# test_rj45-12_THT.net
KiCad netlist of a schematic drawn in EAGLE
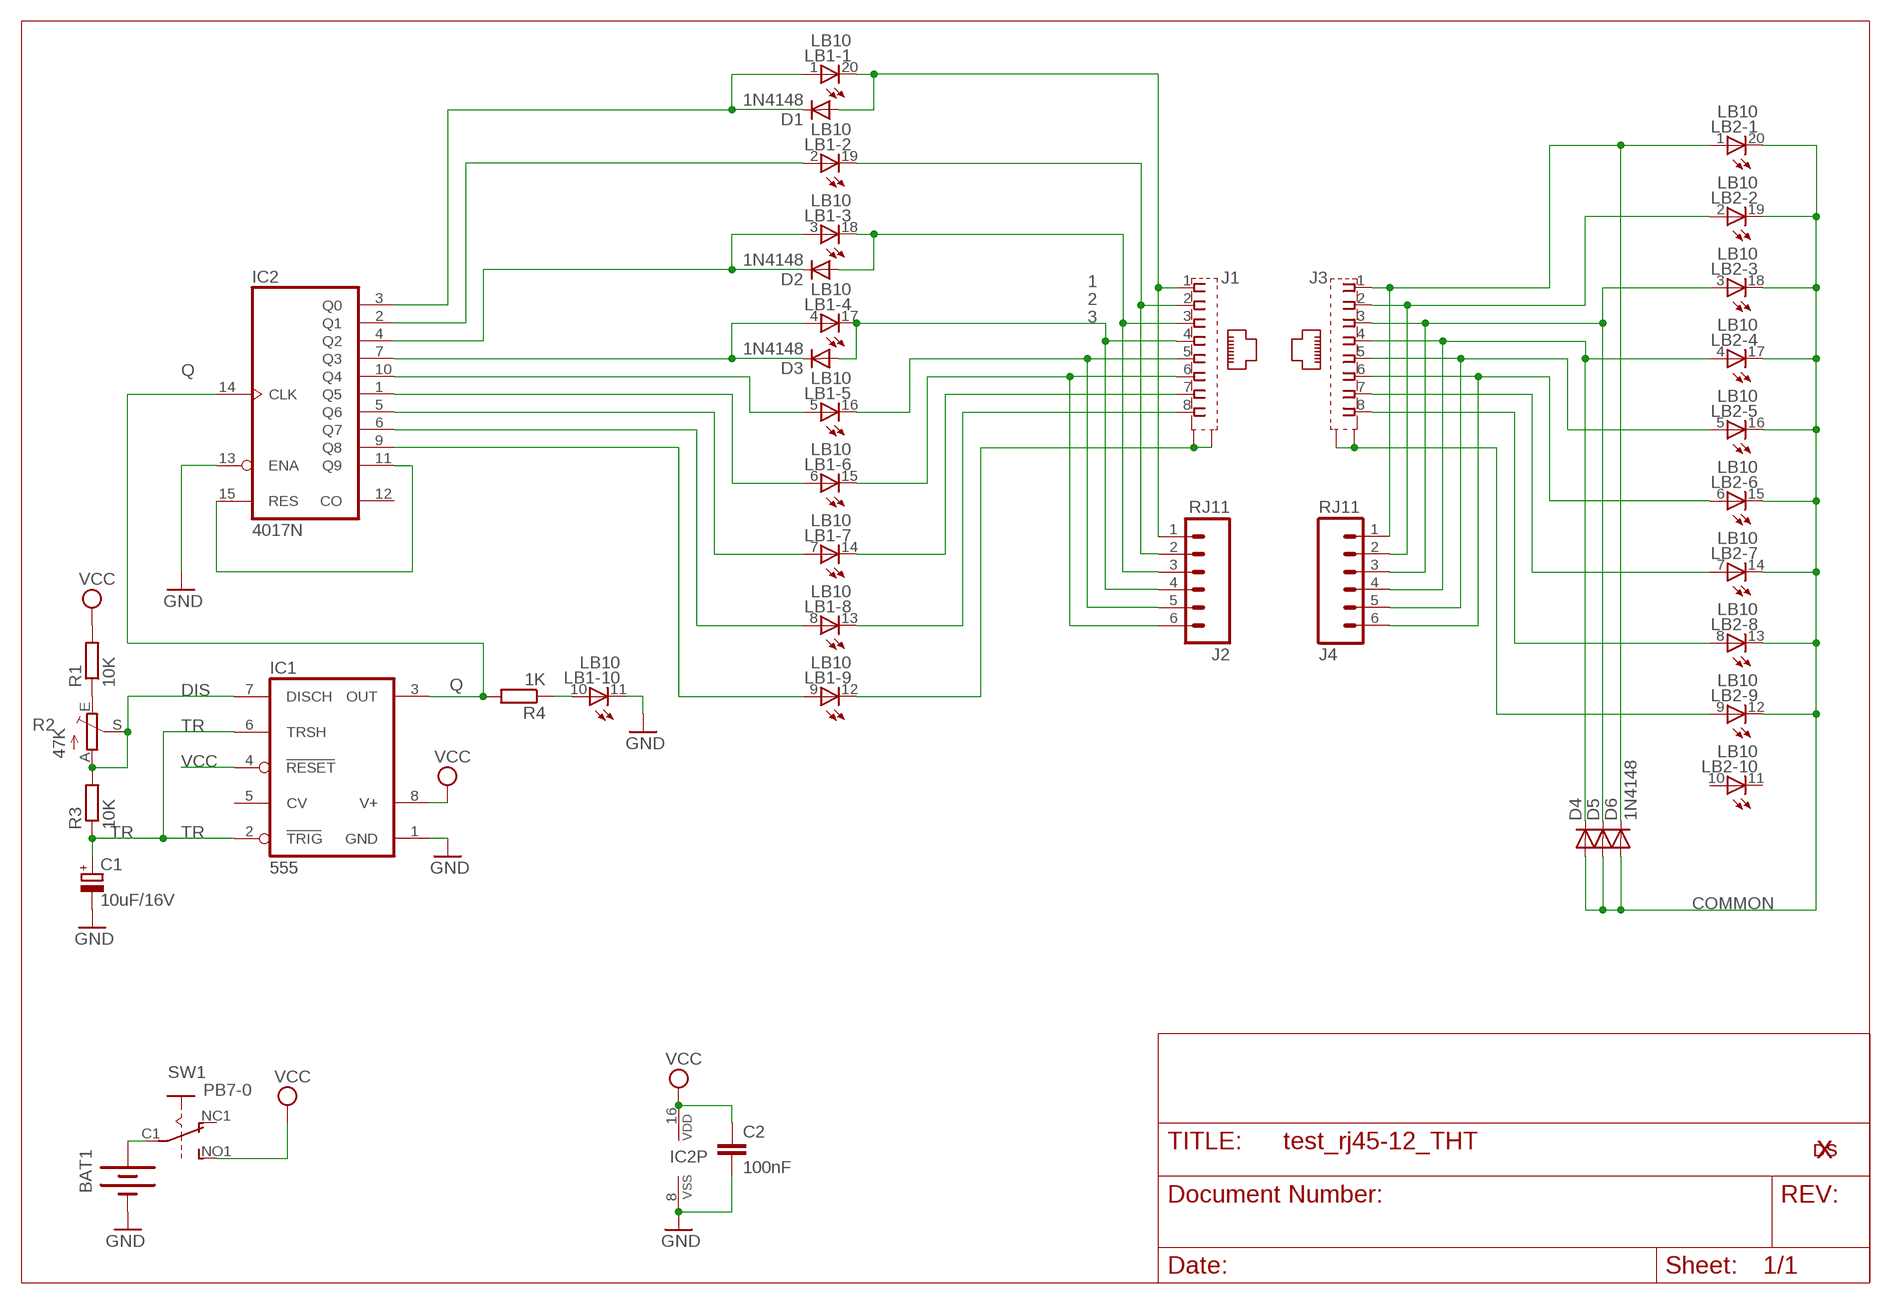
[diagram p0: schematic, sheet 1]

(export (version "E")
  (design (tool "Eeschema 10.0.6"))
  (components
    (comp (ref "$1_23_$")
      (value "XDESIG21")
      (footprint "eagle-import:XDESIG")
      (libsource (lib "eagle-import") (part "XDESIG21"))
    )
    (comp (ref "BAT1")
      (value "BATTERY9V")
      (footprint "eagle-import:BATTCON_9V")
      (libsource (lib "eagle-import") (part "BATTERY9V"))
    )
    (comp (ref "C1")
      (value "10uF/16V")
      (footprint "eagle-import:E2,5-6")
      (libsource (lib "eagle-import") (part "CPOL-EUE2.5-6"))
    )
    (comp (ref "C2")
      (value "100nF")
      (footprint "eagle-import:C2.5-2")
      (libsource (lib "eagle-import") (part "C2.5/2"))
    )
    (comp (ref "D1")
      (value "1N4148")
      (footprint "eagle-import:D-2.5")
      (libsource (lib "eagle-import") (part "DIODE-D-2.5"))
    )
    (comp (ref "D2")
      (value "1N4148")
      (footprint "eagle-import:D-2.5")
      (libsource (lib "eagle-import") (part "DIODE-D-2.5"))
    )
    (comp (ref "D3")
      (value "1N4148")
      (footprint "eagle-import:D-2.5")
      (libsource (lib "eagle-import") (part "DIODE-D-2.5"))
    )
    (comp (ref "D4")
      (value "DIODE-D-2.5")
      (footprint "eagle-import:D-2.5")
      (libsource (lib "eagle-import") (part "DIODE-D-2.5"))
    )
    (comp (ref "D5")
      (value "DIODE-D-2.5")
      (footprint "eagle-import:D-2.5")
      (libsource (lib "eagle-import") (part "DIODE-D-2.5"))
    )
    (comp (ref "D6")
      (value "1N4148")
      (footprint "eagle-import:D-2.5")
      (libsource (lib "eagle-import") (part "DIODE-D-2.5"))
    )
    (comp (ref "IC1")
      (value "555")
      (footprint "eagle-import:DIL08")
      (fields (field (name "MF") "MAXIM") (field (name "MPN") "ICM7555IPA+"))
      (libsource (lib "eagle-import") (part "ICM7555"))
    )
    (comp (ref "IC2")
      (value "4017N")
      (footprint "eagle-import:DIL16")
      (libsource (lib "eagle-import") (part "4017N"))
    )
    (comp (ref "J1")
      (value "555153-1")
      (footprint "eagle-import:555153-1")
      (libsource (lib "eagle-import") (part "555153-1"))
    )
    (comp (ref "J2")
      (value "RJ11")
      (footprint "eagle-import:RJ11-6")
      (libsource (lib "eagle-import") (part "RJ11-6PTH"))
    )
    (comp (ref "J3")
      (value "555153-1")
      (footprint "eagle-import:555153-1")
      (libsource (lib "eagle-import") (part "555153-1"))
    )
    (comp (ref "J4")
      (value "RJ11")
      (footprint "eagle-import:RJ11-6")
      (libsource (lib "eagle-import") (part "RJ11-6PTH"))
    )
    (comp (ref "LB1")
      (value "LB10")
      (footprint "eagle-import:LB10")
      (libsource (lib "eagle-import") (part "LB10"))
    )
    (comp (ref "LB2")
      (value "LB10")
      (footprint "eagle-import:LB10")
      (libsource (lib "eagle-import") (part "LB10"))
    )
    (comp (ref "R1")
      (value "10K")
      (footprint "eagle-import:0204_7")
      (libsource (lib "eagle-import") (part "R-EU_0204/7"))
    )
    (comp (ref "R2")
      (value "47K")
      (footprint "eagle-import:CA6V")
      (libsource (lib "eagle-import") (part "TRIM_EU-CA6V"))
    )
    (comp (ref "R3")
      (value "10K")
      (footprint "eagle-import:0204_7")
      (libsource (lib "eagle-import") (part "R-EU_0204/7"))
    )
    (comp (ref "R4")
      (value "1K")
      (footprint "eagle-import:0204_7")
      (libsource (lib "eagle-import") (part "R-EU_0204/7"))
    )
    (comp (ref "SW1")
      (value "PB7-0")
      (footprint "eagle-import:PB07_0")
      (libsource (lib "eagle-import") (part "PB7-0"))
    )
    (comp (ref "U$6")
      (value "XDESIG5MM")
      (footprint "eagle-import:XDESIG_CU")
      (libsource (lib "eagle-import") (part "XDESIG5MM"))
    )
  )
  (nets
    (net (code "1") (name "/1") (class "Default")
      (node (ref "D1") (pin "A") (pinfunction "A_A") (pintype "passive"))
      (node (ref "J1") (pin "1") (pinfunction "1_1") (pintype "passive"))
      (node (ref "J2") (pin "1") (pinfunction "1_1") (pintype "passive"))
      (node (ref "LB1") (pin "20") (pinfunction "C_20") (pintype "passive"))
    )
    (net (code "2") (name "/2") (class "Default")
      (node (ref "J1") (pin "2") (pinfunction "2_2") (pintype "passive"))
      (node (ref "J2") (pin "2") (pinfunction "2_2") (pintype "passive"))
      (node (ref "LB1") (pin "19") (pinfunction "C_19") (pintype "passive"))
    )
    (net (code "3") (name "/3") (class "Default")
      (node (ref "D2") (pin "A") (pinfunction "A_A") (pintype "passive"))
      (node (ref "J1") (pin "3") (pinfunction "3_3") (pintype "passive"))
      (node (ref "J2") (pin "3") (pinfunction "3_3") (pintype "passive"))
      (node (ref "LB1") (pin "18") (pinfunction "C_18") (pintype "passive"))
    )
    (net (code "4") (name "/COMMON") (class "Default")
      (node (ref "D4") (pin "A") (pinfunction "A_A") (pintype "passive"))
      (node (ref "D5") (pin "A") (pinfunction "A_A") (pintype "passive"))
      (node (ref "D6") (pin "A") (pinfunction "A_A") (pintype "passive"))
      (node (ref "LB2") (pin "12") (pinfunction "C_12") (pintype "passive"))
      (node (ref "LB2") (pin "13") (pinfunction "C_13") (pintype "passive"))
      (node (ref "LB2") (pin "14") (pinfunction "C_14") (pintype "passive"))
      (node (ref "LB2") (pin "15") (pinfunction "C_15") (pintype "passive"))
      (node (ref "LB2") (pin "16") (pinfunction "C_16") (pintype "passive"))
      (node (ref "LB2") (pin "17") (pinfunction "C_17") (pintype "passive"))
      (node (ref "LB2") (pin "18") (pinfunction "C_18") (pintype "passive"))
      (node (ref "LB2") (pin "19") (pinfunction "C_19") (pintype "passive"))
      (node (ref "LB2") (pin "20") (pinfunction "C_20") (pintype "passive"))
    )
    (net (code "5") (name "/DIS") (class "Default")
      (node (ref "IC1") (pin "7") (pinfunction "DISCH_7") (pintype "input"))
      (node (ref "R2") (pin "A") (pinfunction "A_A") (pintype "passive"))
      (node (ref "R2") (pin "S") (pinfunction "S_S") (pintype "passive"))
      (node (ref "R3") (pin "2") (pinfunction "2_2") (pintype "passive"))
    )
    (net (code "6") (name "/Q") (class "Default")
      (node (ref "IC1") (pin "3") (pinfunction "OUT_3") (pintype "output"))
      (node (ref "IC2") (pin "14") (pinfunction "CLK_14") (pintype "input"))
      (node (ref "R4") (pin "2") (pinfunction "2_2") (pintype "passive"))
    )
    (net (code "7") (name "/TR") (class "Default")
      (node (ref "C1") (pin "+") (pinfunction "+_+") (pintype "passive"))
      (node (ref "IC1") (pin "2") (pinfunction "TRIG_2") (pintype "bidirectional"))
      (node (ref "IC1") (pin "6") (pinfunction "TRSH_6") (pintype "input"))
      (node (ref "R3") (pin "1") (pinfunction "1_1") (pintype "passive"))
    )
    (net (code "8") (name "GND") (class "Default")
      (node (ref "BAT1") (pin "-") (pinfunction "-_-") (pintype "power_in"))
      (node (ref "C1") (pin "-") (pinfunction "-_-") (pintype "passive"))
      (node (ref "C2") (pin "2") (pinfunction "2_2") (pintype "passive"))
      (node (ref "IC1") (pin "1") (pinfunction "GND_1") (pintype "power_in"))
      (node (ref "IC2") (pin "13") (pinfunction "ENA_13") (pintype "input"))
      (node (ref "IC2") (pin "8") (pinfunction "VSS_8") (pintype "power_in"))
      (node (ref "LB1") (pin "11") (pinfunction "C_11") (pintype "passive"))
    )
    (net (code "9") (name "Net-(IC2A-Q0)") (class "Default")
      (node (ref "D1") (pin "C") (pinfunction "C_C") (pintype "passive"))
      (node (ref "IC2") (pin "3") (pinfunction "Q0_3") (pintype "output"))
      (node (ref "LB1") (pin "1") (pinfunction "A_1") (pintype "passive"))
    )
    (net (code "10") (name "Net-(IC2A-Q1)") (class "Default")
      (node (ref "IC2") (pin "2") (pinfunction "Q1_2") (pintype "output"))
      (node (ref "LB1") (pin "2") (pinfunction "A_2") (pintype "passive"))
    )
    (net (code "11") (name "Net-(IC2A-Q2)") (class "Default")
      (node (ref "D2") (pin "C") (pinfunction "C_C") (pintype "passive"))
      (node (ref "IC2") (pin "4") (pinfunction "Q2_4") (pintype "output"))
      (node (ref "LB1") (pin "3") (pinfunction "A_3") (pintype "passive"))
    )
    (net (code "12") (name "Net-(IC2A-Q3)") (class "Default")
      (node (ref "D3") (pin "C") (pinfunction "C_C") (pintype "passive"))
      (node (ref "IC2") (pin "7") (pinfunction "Q3_7") (pintype "output"))
      (node (ref "LB1") (pin "4") (pinfunction "A_4") (pintype "passive"))
    )
    (net (code "13") (name "Net-(IC2A-Q4)") (class "Default")
      (node (ref "IC2") (pin "10") (pinfunction "Q4_10") (pintype "output"))
      (node (ref "LB1") (pin "5") (pinfunction "A_5") (pintype "passive"))
    )
    (net (code "14") (name "Net-(IC2A-Q5)") (class "Default")
      (node (ref "IC2") (pin "1") (pinfunction "Q5_1") (pintype "output"))
      (node (ref "LB1") (pin "6") (pinfunction "A_6") (pintype "passive"))
    )
    (net (code "15") (name "Net-(IC2A-Q6)") (class "Default")
      (node (ref "IC2") (pin "5") (pinfunction "Q6_5") (pintype "output"))
      (node (ref "LB1") (pin "7") (pinfunction "A_7") (pintype "passive"))
    )
    (net (code "16") (name "Net-(IC2A-Q7)") (class "Default")
      (node (ref "IC2") (pin "6") (pinfunction "Q7_6") (pintype "output"))
      (node (ref "LB1") (pin "8") (pinfunction "A_8") (pintype "passive"))
    )
    (net (code "17") (name "Net-(IC2A-Q8)") (class "Default")
      (node (ref "IC2") (pin "9") (pinfunction "Q8_9") (pintype "output"))
      (node (ref "LB1") (pin "9") (pinfunction "A_9") (pintype "passive"))
    )
    (net (code "18") (name "Net-(IC2A-Q9)") (class "Default")
      (node (ref "IC2") (pin "11") (pinfunction "Q9_11") (pintype "output"))
      (node (ref "IC2") (pin "15") (pinfunction "RES_15") (pintype "input"))
    )
    (net (code "19") (name "Net-(J1-S1)") (class "Default")
      (node (ref "J1") (pin "G1") (pinfunction "S1_G1") (pintype "passive"))
      (node (ref "J1") (pin "G2") (pinfunction "S2_G2") (pintype "passive"))
      (node (ref "LB1") (pin "12") (pinfunction "C_12") (pintype "passive"))
    )
    (net (code "20") (name "Net-(J3-S1)") (class "Default")
      (node (ref "J3") (pin "G1") (pinfunction "S1_G1") (pintype "passive"))
      (node (ref "J3") (pin "G2") (pinfunction "S2_G2") (pintype "passive"))
      (node (ref "LB2") (pin "9") (pinfunction "A_9") (pintype "passive"))
    )
    (net (code "21") (name "Net-(LB1B-A)") (class "Default")
      (node (ref "LB1") (pin "10") (pinfunction "A_10") (pintype "passive"))
      (node (ref "R4") (pin "1") (pinfunction "1_1") (pintype "passive"))
    )
    (net (code "22") (name "Net-(LB1E-C)") (class "Default")
      (node (ref "D3") (pin "A") (pinfunction "A_A") (pintype "passive"))
      (node (ref "J1") (pin "4") (pinfunction "4_4") (pintype "passive"))
      (node (ref "J2") (pin "4") (pinfunction "4_4") (pintype "passive"))
      (node (ref "LB1") (pin "17") (pinfunction "C_17") (pintype "passive"))
    )
    (net (code "23") (name "Net-(LB1F-C)") (class "Default")
      (node (ref "J1") (pin "5") (pinfunction "5_5") (pintype "passive"))
      (node (ref "J2") (pin "5") (pinfunction "5_5") (pintype "passive"))
      (node (ref "LB1") (pin "16") (pinfunction "C_16") (pintype "passive"))
    )
    (net (code "24") (name "Net-(LB1G-C)") (class "Default")
      (node (ref "J1") (pin "6") (pinfunction "6_6") (pintype "passive"))
      (node (ref "J2") (pin "6") (pinfunction "6_6") (pintype "passive"))
      (node (ref "LB1") (pin "15") (pinfunction "C_15") (pintype "passive"))
    )
    (net (code "25") (name "Net-(LB1H-C)") (class "Default")
      (node (ref "J1") (pin "7") (pinfunction "7_7") (pintype "passive"))
      (node (ref "LB1") (pin "14") (pinfunction "C_14") (pintype "passive"))
    )
    (net (code "26") (name "Net-(LB1I-C)") (class "Default")
      (node (ref "J1") (pin "8") (pinfunction "8_8") (pintype "passive"))
      (node (ref "LB1") (pin "13") (pinfunction "C_13") (pintype "passive"))
    )
    (net (code "27") (name "Net-(LB2A-A)") (class "Default")
      (node (ref "D6") (pin "C") (pinfunction "C_C") (pintype "passive"))
      (node (ref "J3") (pin "1") (pinfunction "1_1") (pintype "passive"))
      (node (ref "J4") (pin "1") (pinfunction "1_1") (pintype "passive"))
      (node (ref "LB2") (pin "1") (pinfunction "A_1") (pintype "passive"))
    )
    (net (code "28") (name "Net-(LB2C-A)") (class "Default")
      (node (ref "J3") (pin "2") (pinfunction "2_2") (pintype "passive"))
      (node (ref "J4") (pin "2") (pinfunction "2_2") (pintype "passive"))
      (node (ref "LB2") (pin "2") (pinfunction "A_2") (pintype "passive"))
    )
    (net (code "29") (name "Net-(LB2D-A)") (class "Default")
      (node (ref "D5") (pin "C") (pinfunction "C_C") (pintype "passive"))
      (node (ref "J3") (pin "3") (pinfunction "3_3") (pintype "passive"))
      (node (ref "J4") (pin "3") (pinfunction "3_3") (pintype "passive"))
      (node (ref "LB2") (pin "3") (pinfunction "A_3") (pintype "passive"))
    )
    (net (code "30") (name "Net-(LB2E-A)") (class "Default")
      (node (ref "D4") (pin "C") (pinfunction "C_C") (pintype "passive"))
      (node (ref "J3") (pin "4") (pinfunction "4_4") (pintype "passive"))
      (node (ref "J4") (pin "4") (pinfunction "4_4") (pintype "passive"))
      (node (ref "LB2") (pin "4") (pinfunction "A_4") (pintype "passive"))
    )
    (net (code "31") (name "Net-(LB2F-A)") (class "Default")
      (node (ref "J3") (pin "5") (pinfunction "5_5") (pintype "passive"))
      (node (ref "J4") (pin "5") (pinfunction "5_5") (pintype "passive"))
      (node (ref "LB2") (pin "5") (pinfunction "A_5") (pintype "passive"))
    )
    (net (code "32") (name "Net-(LB2G-A)") (class "Default")
      (node (ref "J3") (pin "6") (pinfunction "6_6") (pintype "passive"))
      (node (ref "J4") (pin "6") (pinfunction "6_6") (pintype "passive"))
      (node (ref "LB2") (pin "6") (pinfunction "A_6") (pintype "passive"))
    )
    (net (code "33") (name "Net-(LB2H-A)") (class "Default")
      (node (ref "J3") (pin "7") (pinfunction "7_7") (pintype "passive"))
      (node (ref "LB2") (pin "7") (pinfunction "A_7") (pintype "passive"))
    )
    (net (code "34") (name "Net-(LB2I-A)") (class "Default")
      (node (ref "J3") (pin "8") (pinfunction "8_8") (pintype "passive"))
      (node (ref "LB2") (pin "8") (pinfunction "A_8") (pintype "passive"))
    )
    (net (code "35") (name "Net-(R1-Pad1)") (class "Default")
      (node (ref "R1") (pin "1") (pinfunction "1_1") (pintype "passive"))
      (node (ref "R2") (pin "E") (pinfunction "E_E") (pintype "passive"))
    )
    (net (code "36") (name "Net-(SW1A-P)") (class "Default")
      (node (ref "BAT1") (pin "+") (pinfunction "+_+") (pintype "power_in"))
      (node (ref "SW1") (pin "C1") (pinfunction "P_C1") (pintype "passive"))
    )
    (net (code "37") (name "VCC") (class "Default")
      (node (ref "C2") (pin "1") (pinfunction "1_1") (pintype "passive"))
      (node (ref "IC1") (pin "4") (pinfunction "RESET_4") (pintype "input"))
      (node (ref "IC1") (pin "8") (pinfunction "V+_8") (pintype "power_in"))
      (node (ref "IC2") (pin "16") (pinfunction "VDD_16") (pintype "power_in"))
      (node (ref "R1") (pin "2") (pinfunction "2_2") (pintype "passive"))
      (node (ref "SW1") (pin "NO1") (pinfunction "S_NO1") (pintype "passive"))
    )
    (net (code "38") (name "unconnected-(IC1-CV-Pad5)") (class "Default")
      (node (ref "IC1") (pin "5") (pinfunction "CV_5") (pintype "passive"))
    )
    (net (code "39") (name "unconnected-(IC2A-CO-Pad12)") (class "Default")
      (node (ref "IC2") (pin "12") (pinfunction "CO_12") (pintype "output"))
    )
    (net (code "40") (name "unconnected-(LB2B-A-Pad10)") (class "Default")
      (node (ref "LB2") (pin "10") (pinfunction "A_10") (pintype "passive"))
    )
    (net (code "41") (name "unconnected-(LB2B-C-Pad11)") (class "Default")
      (node (ref "LB2") (pin "11") (pinfunction "C_11") (pintype "passive"))
    )
    (net (code "42") (name "unconnected-(SW1A-O-PadNC1)") (class "Default")
      (node (ref "SW1") (pin "NC1") (pinfunction "O_NC1") (pintype "passive"))
    )
  )
)
